# cia2piggy2.net
KiCad netlist of a schematic drawn in EAGLE
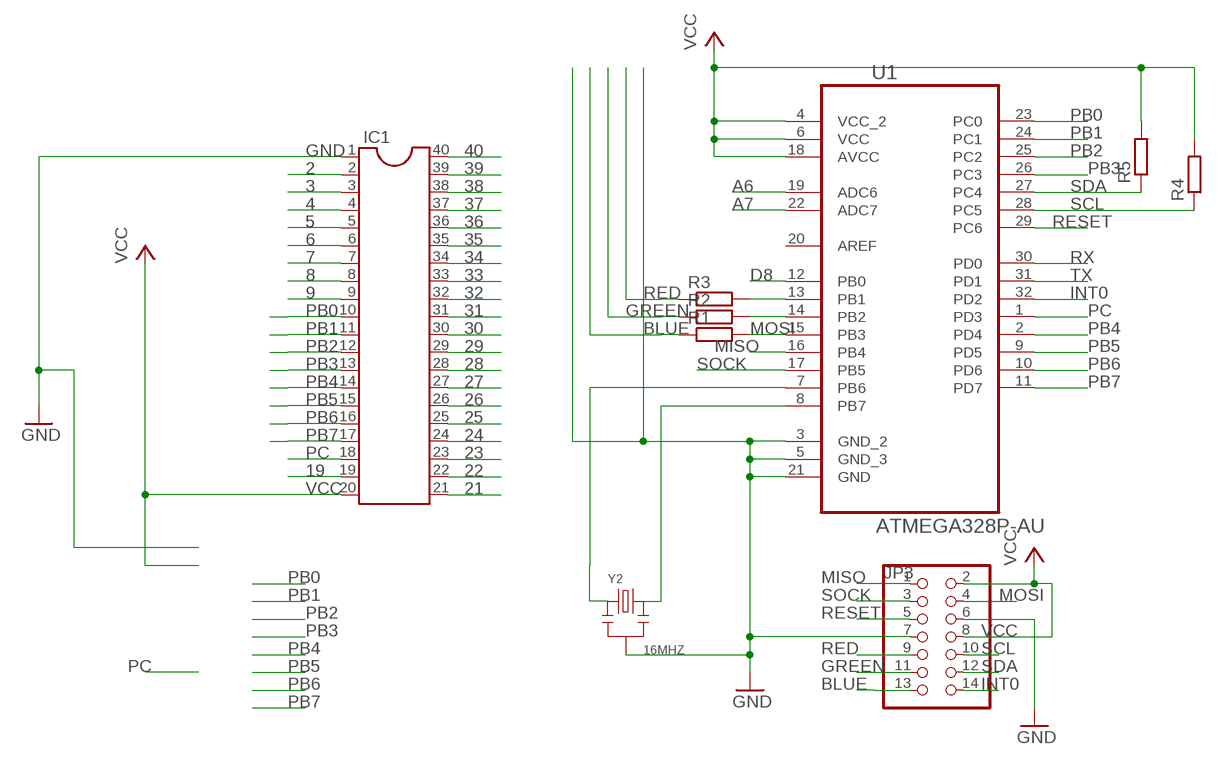
[diagram p0: schematic, sheet 1]

(export (version "E")
  (design (tool "Eeschema 10.0.6"))
  (components
    (comp (ref "IC1")
      (value "DIL40")
      (footprint "eagle-import:DIL40")
      (libsource (lib "eagle-import") (part "DIL40"))
    )
    (comp (ref "JP3")
      (value "PINHD-2X7")
      (footprint "eagle-import:2X07")
      (libsource (lib "eagle-import") (part "PINHD-2X7"))
    )
    (comp (ref "R1")
      (value "R-EU_M0805")
      (footprint "eagle-import:M0805")
      (libsource (lib "eagle-import") (part "R-EU_M0805"))
    )
    (comp (ref "R2")
      (value "R-EU_M0805")
      (footprint "eagle-import:M0805")
      (libsource (lib "eagle-import") (part "R-EU_M0805"))
    )
    (comp (ref "R3")
      (value "R-EU_M0805")
      (footprint "eagle-import:M0805")
      (libsource (lib "eagle-import") (part "R-EU_M0805"))
    )
    (comp (ref "R4")
      (value "R-EU_M0805")
      (footprint "eagle-import:M0805")
      (libsource (lib "eagle-import") (part "R-EU_M0805"))
    )
    (comp (ref "R5")
      (value "R-EU_M0805")
      (footprint "eagle-import:M0805")
      (libsource (lib "eagle-import") (part "R-EU_M0805"))
    )
    (comp (ref "U1")
      (value "ATMEGA328P-AU")
      (footprint "eagle-import:QFP80P900X900X120-32N")
      (libsource (lib "eagle-import") (part "ATMEGA328P-AU"))
    )
    (comp (ref "Y2")
      (value "16MHZ")
      (footprint "eagle-import:X3-SMD-3.6X1.3X0.8MM")
      (libsource (lib "eagle-import") (part "SMD-CRYSTAL-8MHZ--0.3%-150R(3P-3.6X1.3MM)"))
    )
  )
  (nets
    (net (code "1") (name "/2") (class "Default")
      (node (ref "IC1") (pin "2") (pinfunction "2_2") (pintype "passive"))
    )
    (net (code "2") (name "/3") (class "Default")
      (node (ref "IC1") (pin "3") (pinfunction "3_3") (pintype "passive"))
    )
    (net (code "3") (name "/4") (class "Default")
      (node (ref "IC1") (pin "4") (pinfunction "4_4") (pintype "passive"))
    )
    (net (code "4") (name "/5") (class "Default")
      (node (ref "IC1") (pin "5") (pinfunction "5_5") (pintype "passive"))
    )
    (net (code "5") (name "/6") (class "Default")
      (node (ref "IC1") (pin "6") (pinfunction "6_6") (pintype "passive"))
    )
    (net (code "6") (name "/7") (class "Default")
      (node (ref "IC1") (pin "7") (pinfunction "7_7") (pintype "passive"))
    )
    (net (code "7") (name "/8") (class "Default")
      (node (ref "IC1") (pin "8") (pinfunction "8_8") (pintype "passive"))
    )
    (net (code "8") (name "/9") (class "Default")
      (node (ref "IC1") (pin "9") (pinfunction "9_9") (pintype "passive"))
    )
    (net (code "9") (name "/19") (class "Default")
      (node (ref "IC1") (pin "19") (pinfunction "19_19") (pintype "passive"))
    )
    (net (code "10") (name "/21") (class "Default")
      (node (ref "IC1") (pin "21") (pinfunction "21_21") (pintype "passive"))
    )
    (net (code "11") (name "/22") (class "Default")
      (node (ref "IC1") (pin "22") (pinfunction "22_22") (pintype "passive"))
    )
    (net (code "12") (name "/23") (class "Default")
      (node (ref "IC1") (pin "23") (pinfunction "23_23") (pintype "passive"))
    )
    (net (code "13") (name "/24") (class "Default")
      (node (ref "IC1") (pin "24") (pinfunction "24_24") (pintype "passive"))
    )
    (net (code "14") (name "/25") (class "Default")
      (node (ref "IC1") (pin "25") (pinfunction "25_25") (pintype "passive"))
    )
    (net (code "15") (name "/26") (class "Default")
      (node (ref "IC1") (pin "26") (pinfunction "26_26") (pintype "passive"))
    )
    (net (code "16") (name "/27") (class "Default")
      (node (ref "IC1") (pin "27") (pinfunction "27_27") (pintype "passive"))
    )
    (net (code "17") (name "/28") (class "Default")
      (node (ref "IC1") (pin "28") (pinfunction "28_28") (pintype "passive"))
    )
    (net (code "18") (name "/29") (class "Default")
      (node (ref "IC1") (pin "29") (pinfunction "29_29") (pintype "passive"))
    )
    (net (code "19") (name "/30") (class "Default")
      (node (ref "IC1") (pin "30") (pinfunction "30_30") (pintype "passive"))
    )
    (net (code "20") (name "/31") (class "Default")
      (node (ref "IC1") (pin "31") (pinfunction "31_31") (pintype "passive"))
    )
    (net (code "21") (name "/32") (class "Default")
      (node (ref "IC1") (pin "32") (pinfunction "32_32") (pintype "passive"))
    )
    (net (code "22") (name "/33") (class "Default")
      (node (ref "IC1") (pin "33") (pinfunction "33_33") (pintype "passive"))
    )
    (net (code "23") (name "/34") (class "Default")
      (node (ref "IC1") (pin "34") (pinfunction "34_34") (pintype "passive"))
    )
    (net (code "24") (name "/35") (class "Default")
      (node (ref "IC1") (pin "35") (pinfunction "35_35") (pintype "passive"))
    )
    (net (code "25") (name "/36") (class "Default")
      (node (ref "IC1") (pin "36") (pinfunction "36_36") (pintype "passive"))
    )
    (net (code "26") (name "/37") (class "Default")
      (node (ref "IC1") (pin "37") (pinfunction "37_37") (pintype "passive"))
    )
    (net (code "27") (name "/38") (class "Default")
      (node (ref "IC1") (pin "38") (pinfunction "38_38") (pintype "passive"))
    )
    (net (code "28") (name "/39") (class "Default")
      (node (ref "IC1") (pin "39") (pinfunction "39_39") (pintype "passive"))
    )
    (net (code "29") (name "/40") (class "Default")
      (node (ref "IC1") (pin "40") (pinfunction "40_40") (pintype "passive"))
    )
    (net (code "30") (name "/A6") (class "Default")
      (node (ref "U1") (pin "19") (pinfunction "ADC6_19") (pintype "input"))
    )
    (net (code "31") (name "/A7") (class "Default")
      (node (ref "U1") (pin "22") (pinfunction "ADC7_22") (pintype "input"))
    )
    (net (code "32") (name "/BLUE") (class "Default")
      (node (ref "JP3") (pin "13") (pinfunction "13_13") (pintype "passive"))
      (node (ref "R1") (pin "1") (pinfunction "1_1") (pintype "passive"))
    )
    (net (code "33") (name "/D8") (class "Default")
      (node (ref "U1") (pin "12") (pinfunction "PB0_12") (pintype "bidirectional"))
    )
    (net (code "34") (name "/GREEN") (class "Default")
      (node (ref "JP3") (pin "11") (pinfunction "11_11") (pintype "passive"))
      (node (ref "R2") (pin "1") (pinfunction "1_1") (pintype "passive"))
    )
    (net (code "35") (name "/INT0") (class "Default")
      (node (ref "JP3") (pin "14") (pinfunction "14_14") (pintype "passive"))
      (node (ref "U1") (pin "32") (pinfunction "PD2_32") (pintype "bidirectional"))
    )
    (net (code "36") (name "/MISO") (class "Default")
      (node (ref "JP3") (pin "1") (pinfunction "1_1") (pintype "passive"))
      (node (ref "U1") (pin "16") (pinfunction "PB4_16") (pintype "bidirectional"))
    )
    (net (code "37") (name "/MOSI") (class "Default")
      (node (ref "JP3") (pin "4") (pinfunction "4_4") (pintype "passive"))
      (node (ref "R1") (pin "2") (pinfunction "2_2") (pintype "passive"))
      (node (ref "U1") (pin "15") (pinfunction "PB3_15") (pintype "bidirectional"))
    )
    (net (code "38") (name "/PB0") (class "Default")
      (node (ref "IC1") (pin "10") (pinfunction "10_10") (pintype "passive"))
      (node (ref "U1") (pin "23") (pinfunction "PC0_23") (pintype "bidirectional"))
    )
    (net (code "39") (name "/PB1") (class "Default")
      (node (ref "IC1") (pin "11") (pinfunction "11_11") (pintype "passive"))
      (node (ref "U1") (pin "24") (pinfunction "PC1_24") (pintype "bidirectional"))
    )
    (net (code "40") (name "/PB2") (class "Default")
      (node (ref "IC1") (pin "12") (pinfunction "12_12") (pintype "passive"))
      (node (ref "U1") (pin "25") (pinfunction "PC2_25") (pintype "bidirectional"))
    )
    (net (code "41") (name "/PB3") (class "Default")
      (node (ref "IC1") (pin "13") (pinfunction "13_13") (pintype "passive"))
      (node (ref "U1") (pin "26") (pinfunction "PC3_26") (pintype "bidirectional"))
    )
    (net (code "42") (name "/PB4") (class "Default")
      (node (ref "IC1") (pin "14") (pinfunction "14_14") (pintype "passive"))
      (node (ref "U1") (pin "2") (pinfunction "PD4_2") (pintype "bidirectional"))
    )
    (net (code "43") (name "/PB5") (class "Default")
      (node (ref "IC1") (pin "15") (pinfunction "15_15") (pintype "passive"))
      (node (ref "U1") (pin "9") (pinfunction "PD5_9") (pintype "bidirectional"))
    )
    (net (code "44") (name "/PB6") (class "Default")
      (node (ref "IC1") (pin "16") (pinfunction "16_16") (pintype "passive"))
      (node (ref "U1") (pin "10") (pinfunction "PD6_10") (pintype "bidirectional"))
    )
    (net (code "45") (name "/PB7") (class "Default")
      (node (ref "IC1") (pin "17") (pinfunction "17_17") (pintype "passive"))
      (node (ref "U1") (pin "11") (pinfunction "PD7_11") (pintype "bidirectional"))
    )
    (net (code "46") (name "/PC") (class "Default")
      (node (ref "IC1") (pin "18") (pinfunction "18_18") (pintype "passive"))
      (node (ref "U1") (pin "1") (pinfunction "PD3_1") (pintype "bidirectional"))
    )
    (net (code "47") (name "/RED") (class "Default")
      (node (ref "JP3") (pin "9") (pinfunction "9_9") (pintype "passive"))
      (node (ref "R3") (pin "1") (pinfunction "1_1") (pintype "passive"))
    )
    (net (code "48") (name "/RESET") (class "Default")
      (node (ref "JP3") (pin "5") (pinfunction "5_5") (pintype "passive"))
      (node (ref "U1") (pin "29") (pinfunction "PC6_29") (pintype "bidirectional"))
    )
    (net (code "49") (name "/RX") (class "Default")
      (node (ref "U1") (pin "30") (pinfunction "PD0_30") (pintype "bidirectional"))
    )
    (net (code "50") (name "/SCL") (class "Default")
      (node (ref "JP3") (pin "10") (pinfunction "10_10") (pintype "passive"))
      (node (ref "R4") (pin "1") (pinfunction "1_1") (pintype "passive"))
      (node (ref "U1") (pin "28") (pinfunction "PC5_28") (pintype "bidirectional"))
    )
    (net (code "51") (name "/SDA") (class "Default")
      (node (ref "JP3") (pin "12") (pinfunction "12_12") (pintype "passive"))
      (node (ref "R5") (pin "1") (pinfunction "1_1") (pintype "passive"))
      (node (ref "U1") (pin "27") (pinfunction "PC4_27") (pintype "bidirectional"))
    )
    (net (code "52") (name "/SOCK") (class "Default")
      (node (ref "JP3") (pin "3") (pinfunction "3_3") (pintype "passive"))
      (node (ref "U1") (pin "17") (pinfunction "PB5_17") (pintype "bidirectional"))
    )
    (net (code "53") (name "/TX") (class "Default")
      (node (ref "U1") (pin "31") (pinfunction "PD1_31") (pintype "bidirectional"))
    )
    (net (code "54") (name "GND") (class "Default")
      (node (ref "IC1") (pin "1") (pinfunction "1_1") (pintype "passive"))
      (node (ref "JP3") (pin "6") (pinfunction "6_6") (pintype "passive"))
      (node (ref "JP3") (pin "7") (pinfunction "7_7") (pintype "passive"))
      (node (ref "U1") (pin "21") (pinfunction "GND_21") (pintype "passive"))
      (node (ref "U1") (pin "3") (pinfunction "GND_2_3") (pintype "passive"))
      (node (ref "U1") (pin "5") (pinfunction "GND_3_5") (pintype "passive"))
      (node (ref "Y2") (pin "2") (pinfunction "2_2") (pintype "passive"))
    )
    (net (code "55") (name "Net-(U1-PB1)") (class "Default")
      (node (ref "R3") (pin "2") (pinfunction "2_2") (pintype "passive"))
      (node (ref "U1") (pin "13") (pinfunction "PB1_13") (pintype "bidirectional"))
    )
    (net (code "56") (name "Net-(U1-PB2)") (class "Default")
      (node (ref "R2") (pin "2") (pinfunction "2_2") (pintype "passive"))
      (node (ref "U1") (pin "14") (pinfunction "PB2_14") (pintype "bidirectional"))
    )
    (net (code "57") (name "Net-(U1-PB6)") (class "Default")
      (node (ref "U1") (pin "7") (pinfunction "PB6_7") (pintype "bidirectional"))
      (node (ref "Y2") (pin "1") (pinfunction "1_1") (pintype "passive"))
    )
    (net (code "58") (name "Net-(U1-PB7)") (class "Default")
      (node (ref "U1") (pin "8") (pinfunction "PB7_8") (pintype "bidirectional"))
      (node (ref "Y2") (pin "3") (pinfunction "3_3") (pintype "passive"))
    )
    (net (code "59") (name "VCC") (class "Default")
      (node (ref "IC1") (pin "20") (pinfunction "20_20") (pintype "passive"))
      (node (ref "JP3") (pin "2") (pinfunction "2_2") (pintype "passive"))
      (node (ref "JP3") (pin "8") (pinfunction "8_8") (pintype "passive"))
      (node (ref "R4") (pin "2") (pinfunction "2_2") (pintype "passive"))
      (node (ref "R5") (pin "2") (pinfunction "2_2") (pintype "passive"))
      (node (ref "U1") (pin "18") (pinfunction "AVCC_18") (pintype "power_in"))
      (node (ref "U1") (pin "4") (pinfunction "VCC_2_4") (pintype "power_in"))
      (node (ref "U1") (pin "6") (pinfunction "VCC_6") (pintype "power_in"))
    )
    (net (code "60") (name "unconnected-(U1-AREF-Pad20)") (class "Default")
      (node (ref "U1") (pin "20") (pinfunction "AREF_20") (pintype "input"))
    )
  )
)
